# 1_PowerSupply.net
KiCad netlist of a schematic drawn in Altium Designer
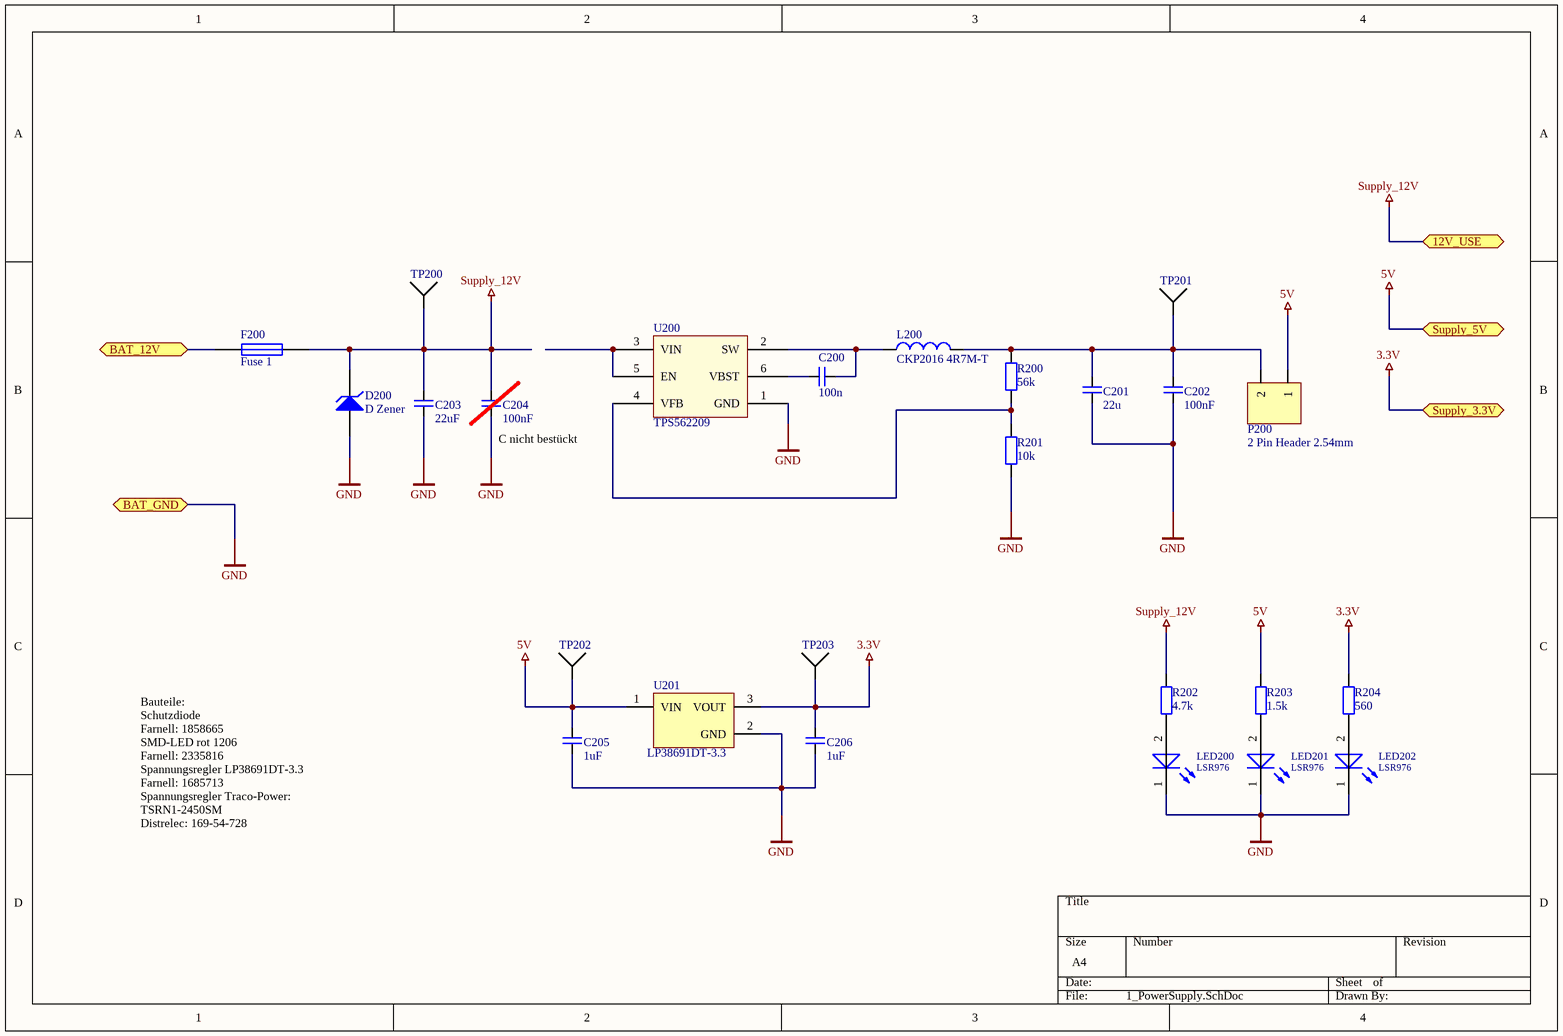
[diagram p0: 1_PowerSupply.SchDoc]

(export (version "E")
  (design (tool "Eeschema 10.0.6"))
  (components
    (comp (ref "C200")
      (value "100n")
      (footprint "CAPC0805")
      (description "X7R MLCC 0805 (2012 Metric)")
      (fields (field (name "TOLERANCE") "10%"))
      (libsource (lib "Motortreiber") (part "C Bipolar 0805"))
    )
    (comp (ref "C201")
      (value "22u")
      (footprint "C0805")
      (description "X7R MLCC 1206 (3016 Metric)")
      (fields (field (name "TOLERANCE") "10%"))
      (libsource (lib "Motortreiber") (part "C Bipolar 1206"))
    )
    (comp (ref "C202")
      (value "100nF")
      (footprint "C0805")
      (description "X7R MLCC 1206 (3016 Metric)")
      (fields (field (name "TOLERANCE") "10%"))
      (libsource (lib "Motortreiber") (part "C Bipolar 1206"))
    )
    (comp (ref "C203")
      (value "22uF")
      (footprint "CAPC0805")
      (description "X7R MLCC 0805 (2012 Metric)")
      (fields (field (name "TOLERANCE") "10%"))
      (libsource (lib "Motortreiber") (part "C Bipolar 0805"))
    )
    (comp (ref "C204")
      (value "100nF")
      (footprint "CAPC0805")
      (description "X7R MLCC 0805 (2012 Metric)")
      (fields (field (name "TOLERANCE") "10%"))
      (libsource (lib "Motortreiber") (part "C Bipolar 0805"))
    )
    (comp (ref "C205")
      (value "1uF")
      (footprint "CAPC0805")
      (description "X7R MLCC 0805 (2012 Metric)")
      (fields (field (name "TOLERANCE") "10%"))
      (libsource (lib "Motortreiber") (part "C Bipolar 0805"))
    )
    (comp (ref "C206")
      (value "1uF")
      (footprint "CAPC0805")
      (description "X7R MLCC 0805 (2012 Metric)")
      (fields (field (name "TOLERANCE") "10%"))
      (libsource (lib "Motortreiber") (part "C Bipolar 0805"))
    )
    (comp (ref "D200")
      (value "D Zener")
      (footprint "SMD_2Pin")
      (description "Zener Diode")
      (fields (field (name "PUBLISHER") "Altium Limited"))
      (libsource (lib "Miscellaneous Devices") (part "D Zener"))
    )
    (comp (ref "F200")
      (value "Fuse 1")
      (footprint "Connector_2")
      (description "Fuse")
      (fields (field (name "PUBLISHER") "Altium Limited"))
      (libsource (lib "Miscellaneous Devices") (part "Fuse 1"))
    )
    (comp (ref "L200")
      (value "CKP2016 4R7M-T")
      (footprint "IND0806")
      (description "MULTILAYER CHIP POWER INDUCTORS")
      (libsource (lib "altium-import") (part "root_0_L_"))
    )
    (comp (ref "LED200")
      (value "LSR976")
      (footprint "CAPC1206")
      (description "Hyper ChipLED, Red,")
      (fields (field (name "MANUFACTURER") "OSRAM") (field (name "PUBLISHER") "Stefan Ursella, M.Eng"))
      (libsource (lib "SysP2015") (part "OSR_LSR976_0805(1K2A)"))
    )
    (comp (ref "LED201")
      (value "LSR976")
      (footprint "CAPC1206")
      (description "Hyper ChipLED, Red,")
      (fields (field (name "MANUFACTURER") "OSRAM") (field (name "PUBLISHER") "Stefan Ursella, M.Eng"))
      (libsource (lib "SysP2015") (part "OSR_LSR976_0805(1K2A)"))
    )
    (comp (ref "LED202")
      (value "LSR976")
      (footprint "CAPC1206")
      (description "Hyper ChipLED, Red,")
      (fields (field (name "MANUFACTURER") "OSRAM") (field (name "PUBLISHER") "Stefan Ursella, M.Eng"))
      (libsource (lib "SysP2015") (part "OSR_LSR976_0805(1K2A)"))
    )
    (comp (ref "P200")
      (value "2 Pin Header 2.54mm")
      (footprint "2Pin Header 2.54mm")
      (libsource (lib "altium-import") (part "root_3_2 Pin Connector_"))
    )
    (comp (ref "R200")
      (value "56k")
      (footprint "GEN_R0805_H")
      (description "generic resistor")
      (fields
        (field (name "MANUFACTURER") "Tbd")
        (field (name "Comment") "Generic")
        (field (name "PUBLISHER") "Altium Limited")
      )
      (libsource (lib "Motortreiber") (part "GEN_R_2"))
    )
    (comp (ref "R201")
      (value "10k")
      (footprint "GEN_R0805_H")
      (description "generic resistor")
      (fields
        (field (name "MANUFACTURER") "Tbd")
        (field (name "Comment") "Generic")
        (field (name "PUBLISHER") "Altium Limited")
      )
      (libsource (lib "Motortreiber") (part "GEN_R_2"))
    )
    (comp (ref "R202")
      (value "4.7k")
      (footprint "GEN_R0805_H")
      (description "generic resistor")
      (fields
        (field (name "MANUFACTURER") "Tbd")
        (field (name "Comment") "Generic")
        (field (name "PUBLISHER") "Altium Limited")
      )
      (libsource (lib "Motortreiber") (part "GEN_R_2"))
    )
    (comp (ref "R203")
      (value "1.5k")
      (footprint "GEN_R0805_H")
      (description "generic resistor")
      (fields
        (field (name "MANUFACTURER") "Tbd")
        (field (name "Comment") "Generic")
        (field (name "PUBLISHER") "Altium Limited")
      )
      (libsource (lib "Motortreiber") (part "GEN_R_2"))
    )
    (comp (ref "R204")
      (value "560")
      (footprint "GEN_R0805_H")
      (description "generic resistor")
      (fields
        (field (name "MANUFACTURER") "Tbd")
        (field (name "Comment") "Generic")
        (field (name "PUBLISHER") "Altium Limited")
      )
      (libsource (lib "Motortreiber") (part "GEN_R_2"))
    )
    (comp (ref "TP200")
      (value "Testpunkt 1mm")
      (footprint "GEN_TP-THT-1.1mm_1_H")
      (fields (field (name "MANUFACTURER") "Keystone Electronics") (field (name "PUBLISHER") "B.Sc. Ursella"))
      (libsource (lib "IR-Sensor") (part "Testpunkt 1mm"))
    )
    (comp (ref "TP201")
      (value "Testpunkt 1mm")
      (footprint "GEN_TP-THT-1.1mm_1_H")
      (fields (field (name "MANUFACTURER") "Keystone Electronics") (field (name "PUBLISHER") "B.Sc. Ursella"))
      (libsource (lib "IR-Sensor") (part "Testpunkt 1mm"))
    )
    (comp (ref "TP202")
      (value "Testpunkt 1mm")
      (footprint "GEN_TP-THT-1.1mm_1_H")
      (fields (field (name "MANUFACTURER") "Keystone Electronics") (field (name "PUBLISHER") "B.Sc. Ursella"))
      (libsource (lib "IR-Sensor") (part "Testpunkt 1mm"))
    )
    (comp (ref "TP203")
      (value "Testpunkt 1mm")
      (footprint "GEN_TP-THT-1.1mm_1_H")
      (fields (field (name "MANUFACTURER") "Keystone Electronics") (field (name "PUBLISHER") "B.Sc. Ursella"))
      (libsource (lib "IR-Sensor") (part "Testpunkt 1mm"))
    )
    (comp (ref "U200")
      (value "TPS562209")
      (footprint "SOT23-6")
      (description "3-A Synchronous Step-Down Voltage Regulator")
      (libsource (lib "altium-import") (part "root_0_TPS562209_"))
    )
    (comp (ref "U201")
      (value "LP38691DT-3.3")
      (footprint "TO_252_3")
      (description "Low Quiescent Current LDO, 3-Pin SOT-89, Extended Temperature, Tape and Reel")
      (fields (field (name "PUBLISHER") "Altium Limited"))
      (libsource (lib "Microchip Power Mgt Line Regulator") (part "MCP1700T-2302E/MB"))
    )
  )
  (nets
    (net (code "1") (name "/BAT_12V") (class "Default")
      (node (ref "F200") (pin "1") (pinfunction "1_1") (pintype "passive"))
    )
    (net (code "2") (name "3.3V") (class "Default")
      (node (ref "C206") (pin "1") (pinfunction "1_1") (pintype "passive"))
      (node (ref "R204") (pin "2") (pinfunction "2_2") (pintype "passive"))
      (node (ref "TP203") (pin "1") (pinfunction "0_1") (pintype "passive"))
      (node (ref "U201") (pin "3") (pinfunction "VOUT_3") (pintype "power_in"))
    )
    (net (code "3") (name "5V") (class "Default")
      (node (ref "C205") (pin "1") (pinfunction "1_1") (pintype "passive"))
      (node (ref "P200") (pin "1") (pinfunction "1_1") (pintype "passive"))
      (node (ref "R203") (pin "2") (pinfunction "2_2") (pintype "passive"))
      (node (ref "TP202") (pin "1") (pinfunction "0_1") (pintype "passive"))
      (node (ref "U201") (pin "1") (pinfunction "VIN_1") (pintype "power_in"))
    )
    (net (code "4") (name "GND") (class "Default")
      (node (ref "C201") (pin "2") (pinfunction "2_2") (pintype "passive"))
      (node (ref "C202") (pin "2") (pinfunction "2_2") (pintype "passive"))
      (node (ref "C203") (pin "2") (pinfunction "2_2") (pintype "passive"))
      (node (ref "C204") (pin "2") (pinfunction "2_2") (pintype "passive"))
      (node (ref "C205") (pin "2") (pinfunction "2_2") (pintype "passive"))
      (node (ref "C206") (pin "2") (pinfunction "2_2") (pintype "passive"))
      (node (ref "D200") (pin "1") (pinfunction "A_1") (pintype "passive"))
      (node (ref "LED200") (pin "1") (pinfunction "K_1") (pintype "passive"))
      (node (ref "LED201") (pin "1") (pinfunction "K_1") (pintype "passive"))
      (node (ref "LED202") (pin "1") (pinfunction "K_1") (pintype "passive"))
      (node (ref "R201") (pin "1") (pinfunction "1_1") (pintype "passive"))
      (node (ref "U200") (pin "1") (pinfunction "GND_1") (pintype "passive"))
      (node (ref "U201") (pin "2") (pinfunction "GND_2") (pintype "power_in"))
    )
    (net (code "5") (name "Net-(LED200-A)") (class "Default")
      (node (ref "LED200") (pin "2") (pinfunction "A_2") (pintype "passive"))
      (node (ref "R202") (pin "1") (pinfunction "1_1") (pintype "passive"))
    )
    (net (code "6") (name "Net-(LED201-A)") (class "Default")
      (node (ref "LED201") (pin "2") (pinfunction "A_2") (pintype "passive"))
      (node (ref "R203") (pin "1") (pinfunction "1_1") (pintype "passive"))
    )
    (net (code "7") (name "Net-(LED202-A)") (class "Default")
      (node (ref "LED202") (pin "2") (pinfunction "A_2") (pintype "passive"))
      (node (ref "R204") (pin "1") (pinfunction "1_1") (pintype "passive"))
    )
    (net (code "8") (name "Net-(TP201-0)") (class "Default")
      (node (ref "C201") (pin "1") (pinfunction "1_1") (pintype "passive"))
      (node (ref "C202") (pin "1") (pinfunction "1_1") (pintype "passive"))
      (node (ref "L200") (pin "2") (pinfunction "2_2") (pintype "passive"))
      (node (ref "P200") (pin "2") (pinfunction "2_2") (pintype "passive"))
      (node (ref "R200") (pin "2") (pinfunction "2_2") (pintype "passive"))
      (node (ref "TP201") (pin "1") (pinfunction "0_1") (pintype "passive"))
    )
    (net (code "9") (name "Net-(U200-EN)") (class "Default")
      (node (ref "U200") (pin "3") (pinfunction "VIN_3") (pintype "passive"))
      (node (ref "U200") (pin "5") (pinfunction "EN_5") (pintype "passive"))
    )
    (net (code "10") (name "Net-(U200-SW)") (class "Default")
      (node (ref "C200") (pin "2") (pinfunction "2_2") (pintype "passive"))
      (node (ref "L200") (pin "1") (pinfunction "1_1") (pintype "passive"))
      (node (ref "U200") (pin "2") (pinfunction "SW_2") (pintype "passive"))
    )
    (net (code "11") (name "Net-(U200-VBST)") (class "Default")
      (node (ref "C200") (pin "1") (pinfunction "1_1") (pintype "passive"))
      (node (ref "U200") (pin "6") (pinfunction "VBST_6") (pintype "passive"))
    )
    (net (code "12") (name "Net-(U200-VFB)") (class "Default")
      (node (ref "R200") (pin "1") (pinfunction "1_1") (pintype "passive"))
      (node (ref "R201") (pin "2") (pinfunction "2_2") (pintype "passive"))
      (node (ref "U200") (pin "4") (pinfunction "VFB_4") (pintype "passive"))
    )
    (net (code "13") (name "Supply_12V") (class "Default")
      (node (ref "C203") (pin "1") (pinfunction "1_1") (pintype "passive"))
      (node (ref "C204") (pin "1") (pinfunction "1_1") (pintype "passive"))
      (node (ref "D200") (pin "2") (pinfunction "K_2") (pintype "passive"))
      (node (ref "F200") (pin "2") (pinfunction "2_2") (pintype "passive"))
      (node (ref "R202") (pin "2") (pinfunction "2_2") (pintype "passive"))
      (node (ref "TP200") (pin "1") (pinfunction "0_1") (pintype "passive"))
    )
  )
)
